# SingleFader.net
KiCad netlist of a schematic drawn in EAGLE
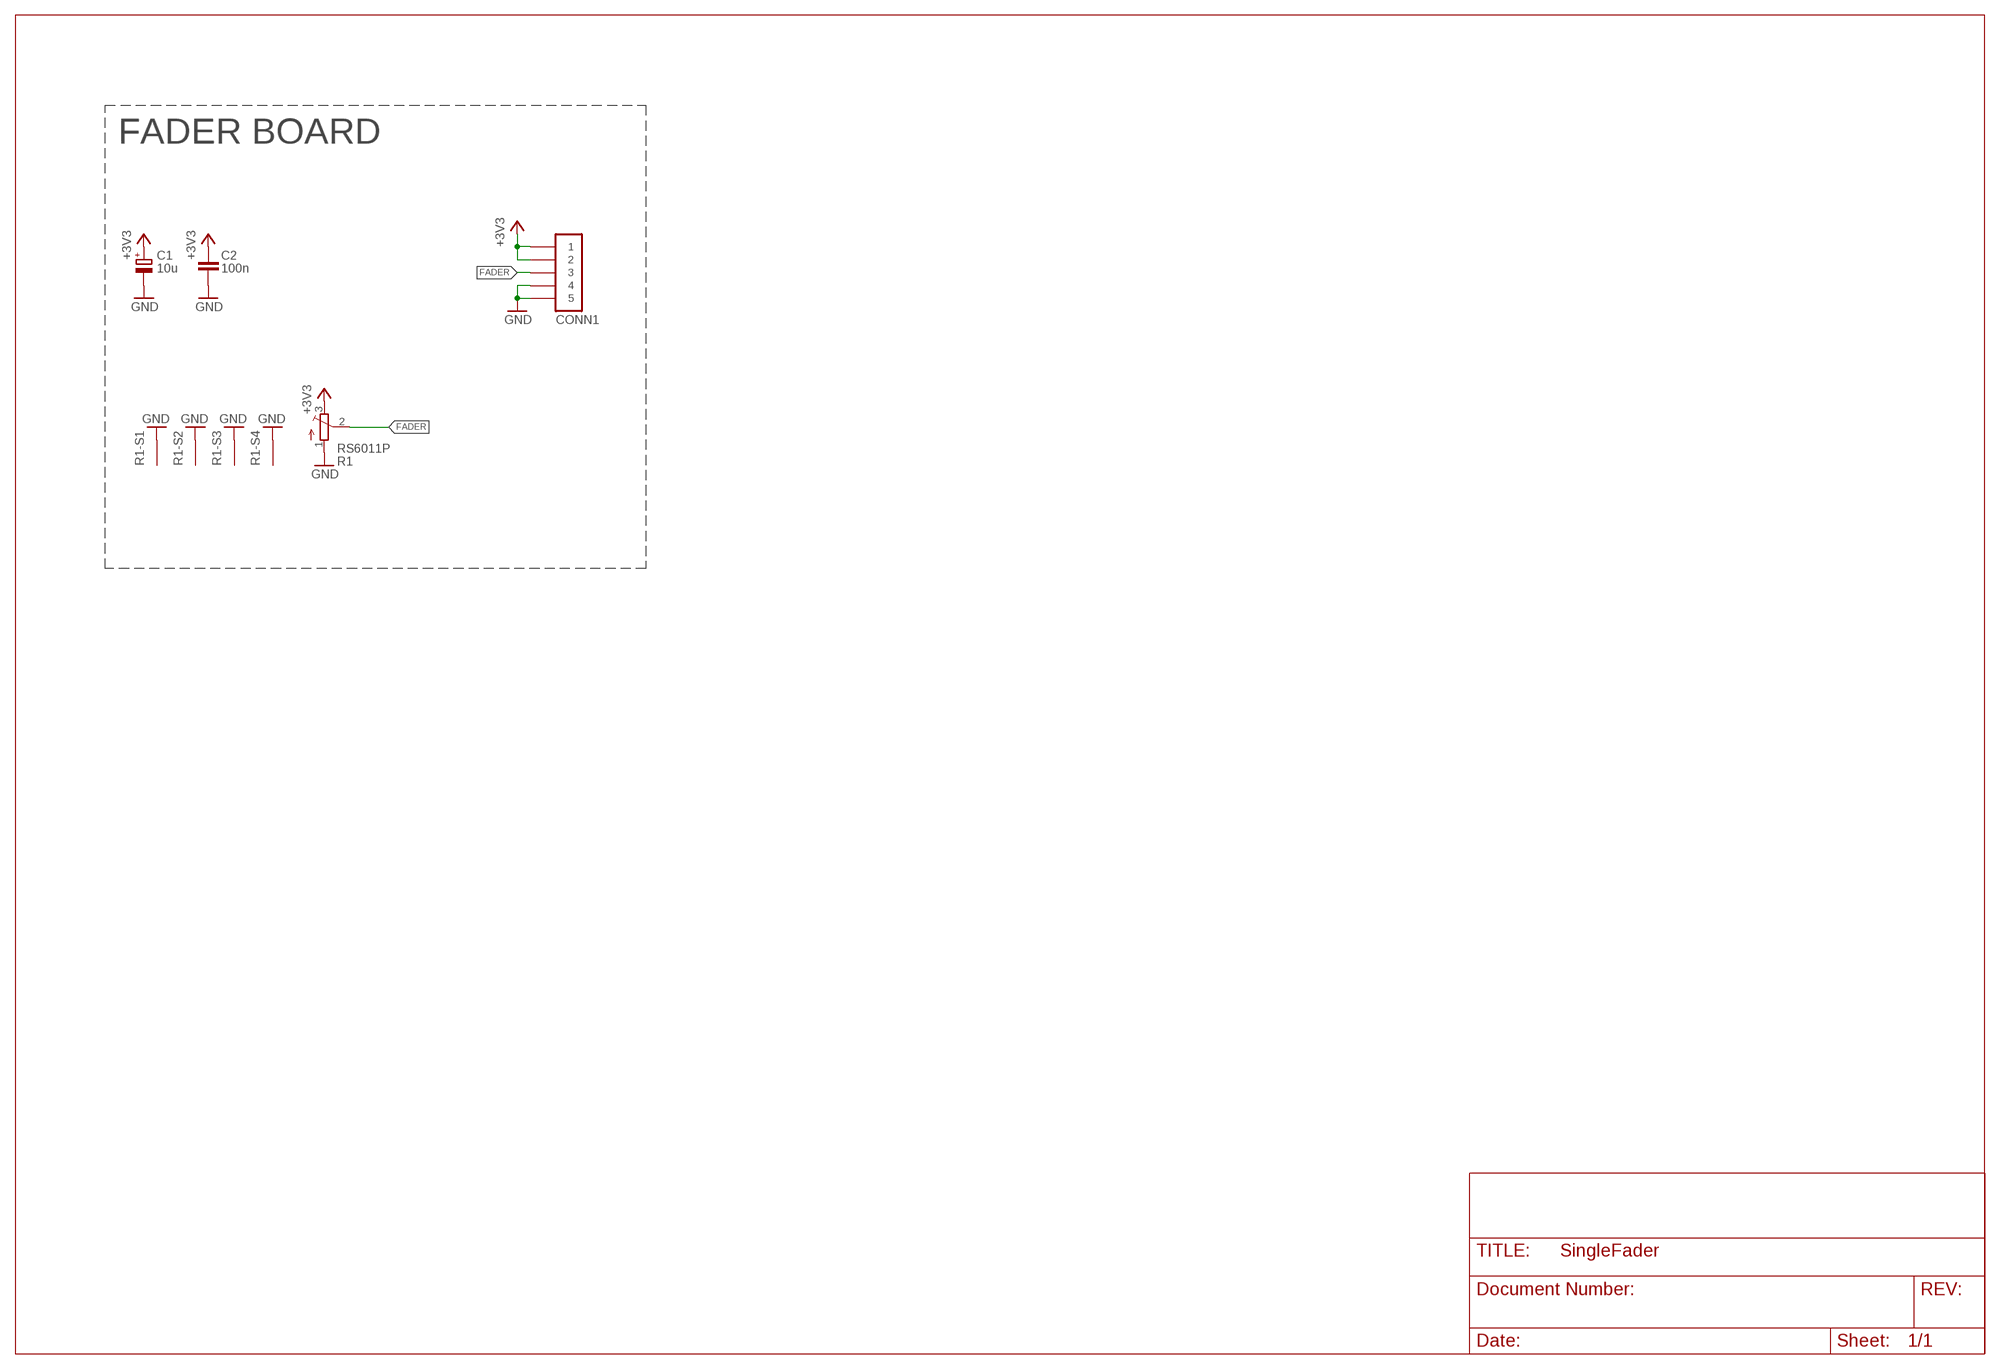
[diagram p0: schematic, sheet 1]

(export (version "E")
  (design (tool "Eeschema 10.0.6"))
  (components
    (comp (ref "C1")
      (value "10u")
      (footprint "eagle-import:153CLV-0405")
      (fields (field (name "MANUFACTURER") "Multicomp") (field (name "MPN") "MCVVT016M100CA1L"))
      (libsource (lib "eagle-import") (part "ELECTROLYTIC_CAPACITOR-CLV-040516V"))
    )
    (comp (ref "C2")
      (value "100n")
      (footprint "eagle-import:C0805")
      (libsource (lib "eagle-import") (part "CAPACITOR-0805"))
    )
    (comp (ref "CONN1")
      (value "PINHD-1X05-FFC-1MM-Z")
      (footprint "eagle-import:MOLEX-52271-0579")
      (fields (field (name "MANUFACTURER") "Molex") (field (name "MPN") "52271-0579"))
      (libsource (lib "eagle-import") (part "PINHD-1X05-FFC-1MM-Z"))
    )
    (comp (ref "R1")
      (value "RS6011P")
      (footprint "eagle-import:RS6011_P")
      (libsource (lib "eagle-import") (part "RS6011P"))
    )
  )
  (nets
    (net (code "1") (name "+3V3") (class "Default")
      (node (ref "C1") (pin "+") (pinfunction "+_+") (pintype "passive"))
      (node (ref "C2") (pin "1") (pinfunction "1_1") (pintype "passive"))
      (node (ref "CONN1") (pin "1") (pinfunction "1_1") (pintype "passive"))
      (node (ref "CONN1") (pin "2") (pinfunction "2_2") (pintype "passive"))
      (node (ref "R1") (pin "3") (pinfunction "3_3") (pintype "passive"))
    )
    (net (code "2") (name "FADER") (class "Default")
      (node (ref "CONN1") (pin "3") (pinfunction "3_3") (pintype "passive"))
      (node (ref "R1") (pin "2") (pinfunction "2_2") (pintype "passive"))
    )
    (net (code "3") (name "GND") (class "Default")
      (node (ref "C1") (pin "-") (pinfunction "-_-") (pintype "passive"))
      (node (ref "C2") (pin "2") (pinfunction "2_2") (pintype "passive"))
      (node (ref "CONN1") (pin "4") (pinfunction "4_4") (pintype "passive"))
      (node (ref "CONN1") (pin "5") (pinfunction "5_5") (pintype "passive"))
      (node (ref "R1") (pin "1") (pinfunction "1_1") (pintype "passive"))
      (node (ref "R1") (pin "S1") (pinfunction "S_S1") (pintype "passive"))
      (node (ref "R1") (pin "S2") (pinfunction "S_S2") (pintype "passive"))
      (node (ref "R1") (pin "S3") (pinfunction "S_S3") (pintype "passive"))
      (node (ref "R1") (pin "S4") (pinfunction "S_S4") (pintype "passive"))
    )
  )
)
